# SCH_MIW_PCB_No_PS_2022-01-17.net
KiCad netlist of a schematic drawn in EasyEDA
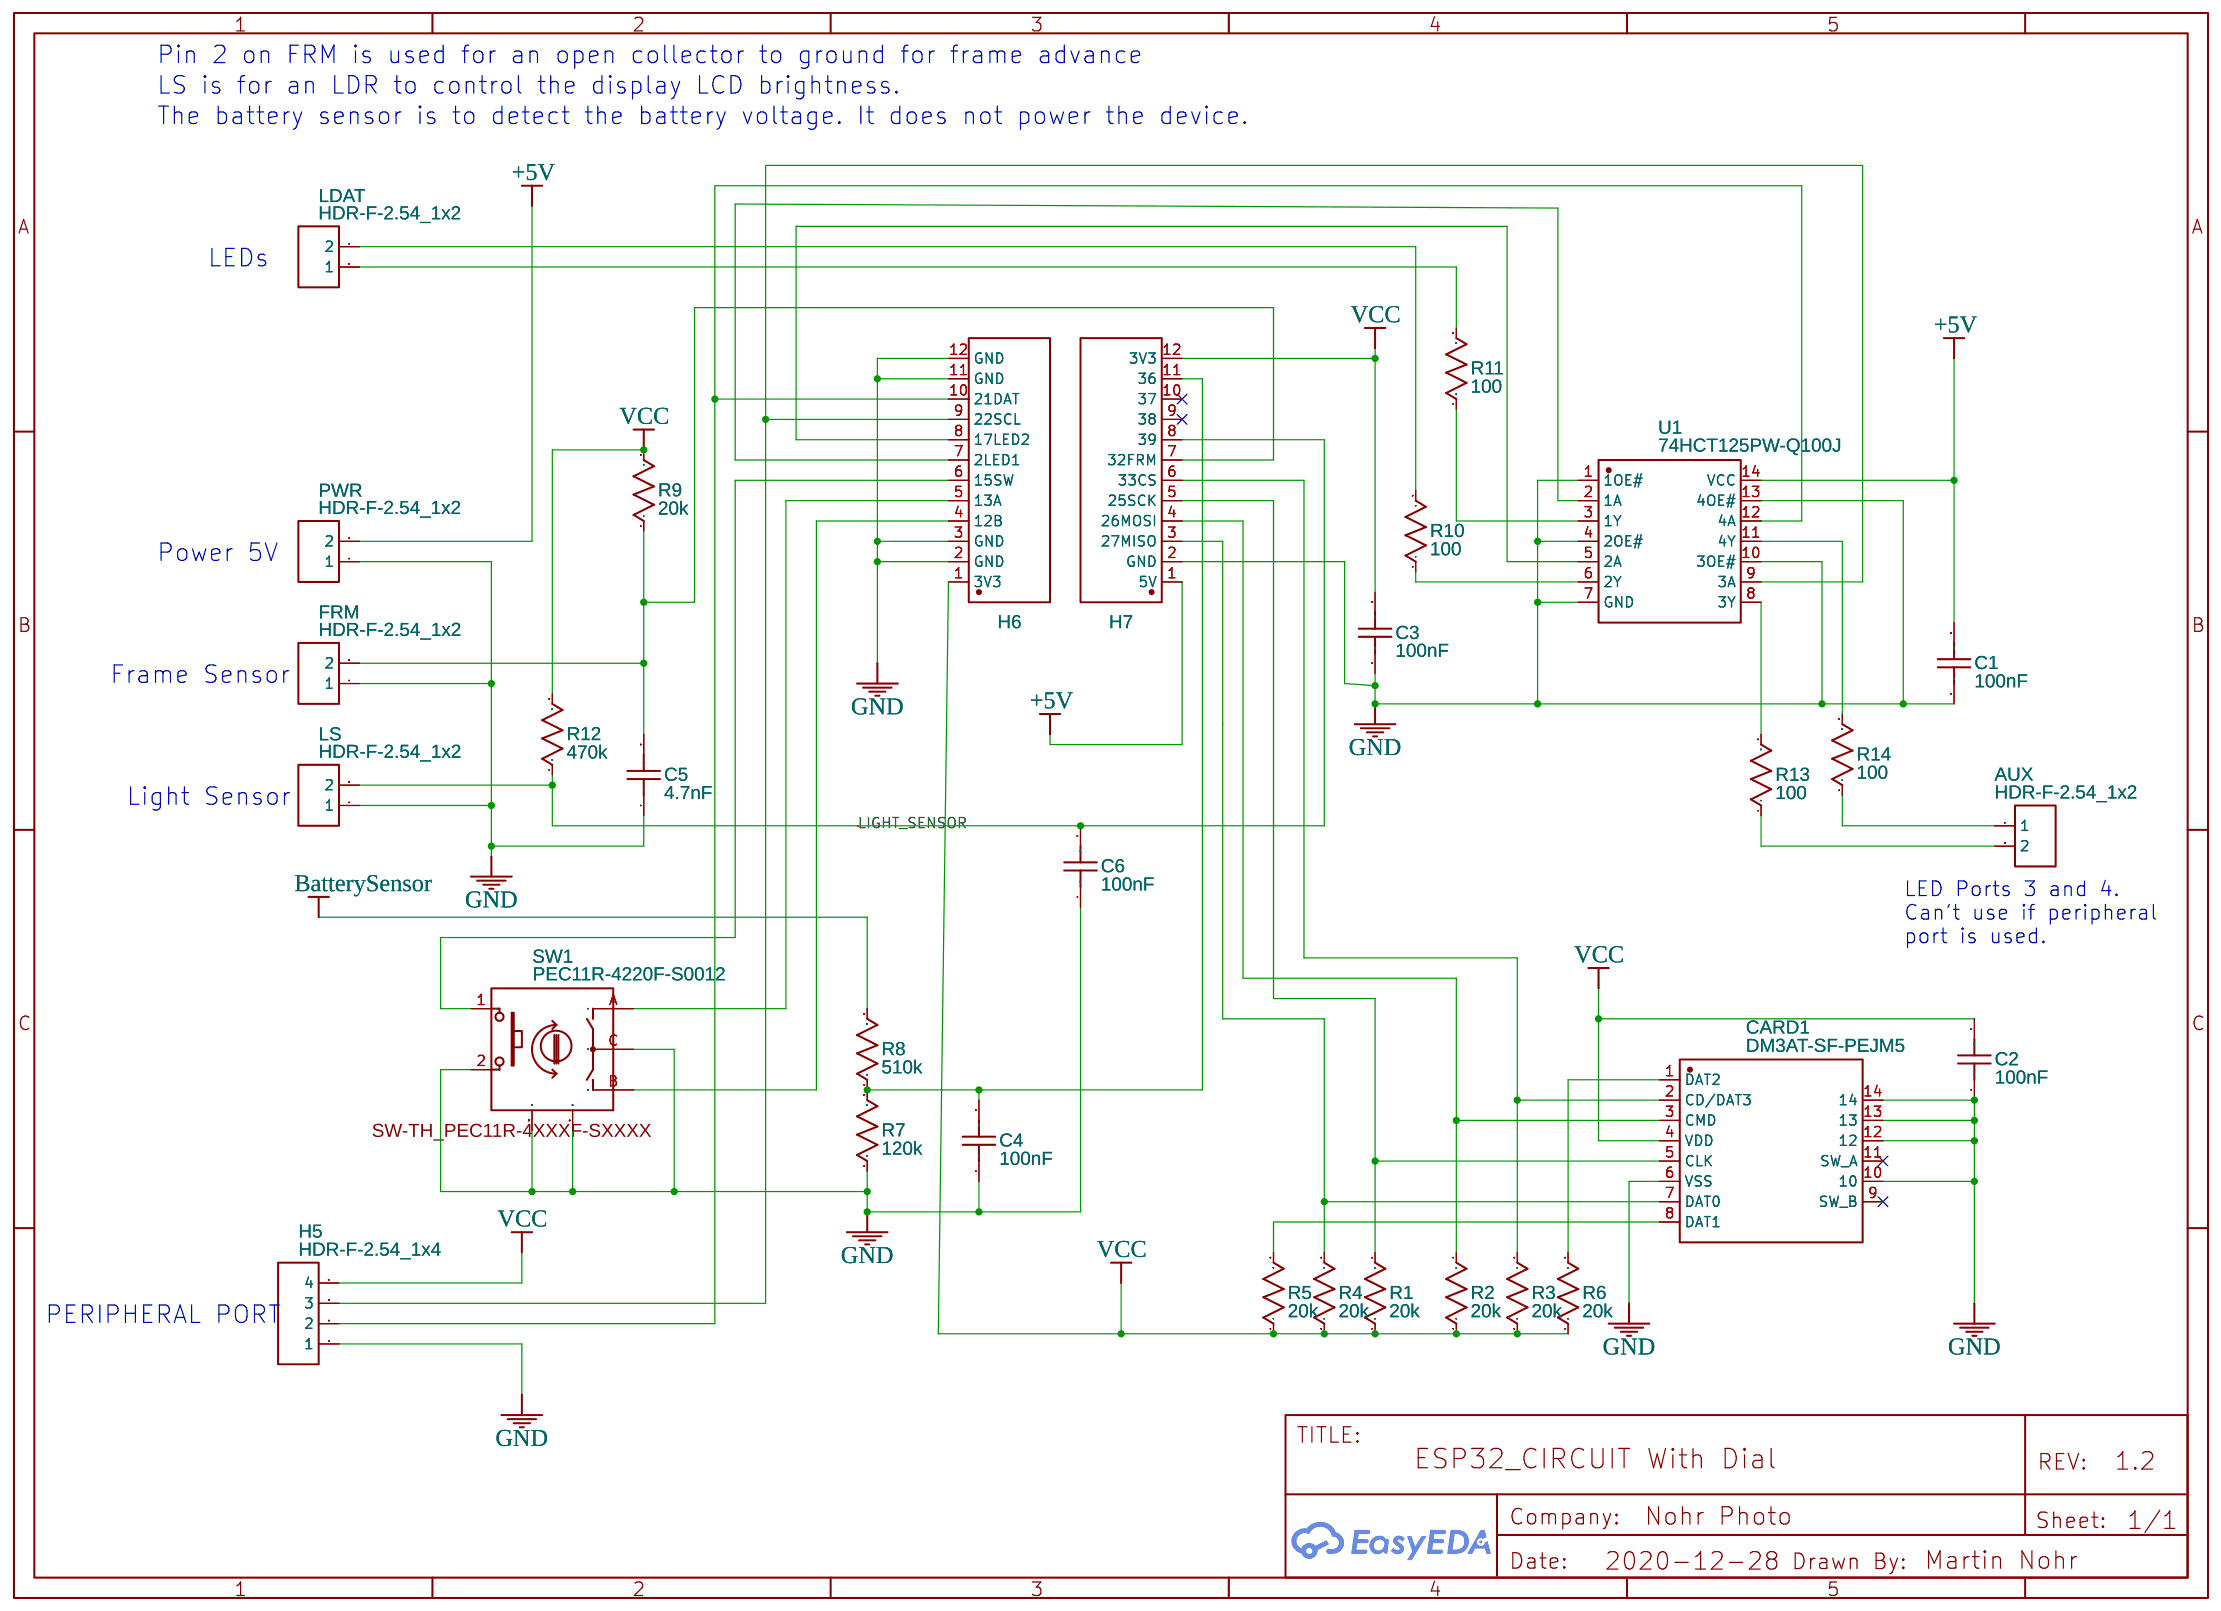
[diagram p0: TTGO_CIRCUIT_PCB]
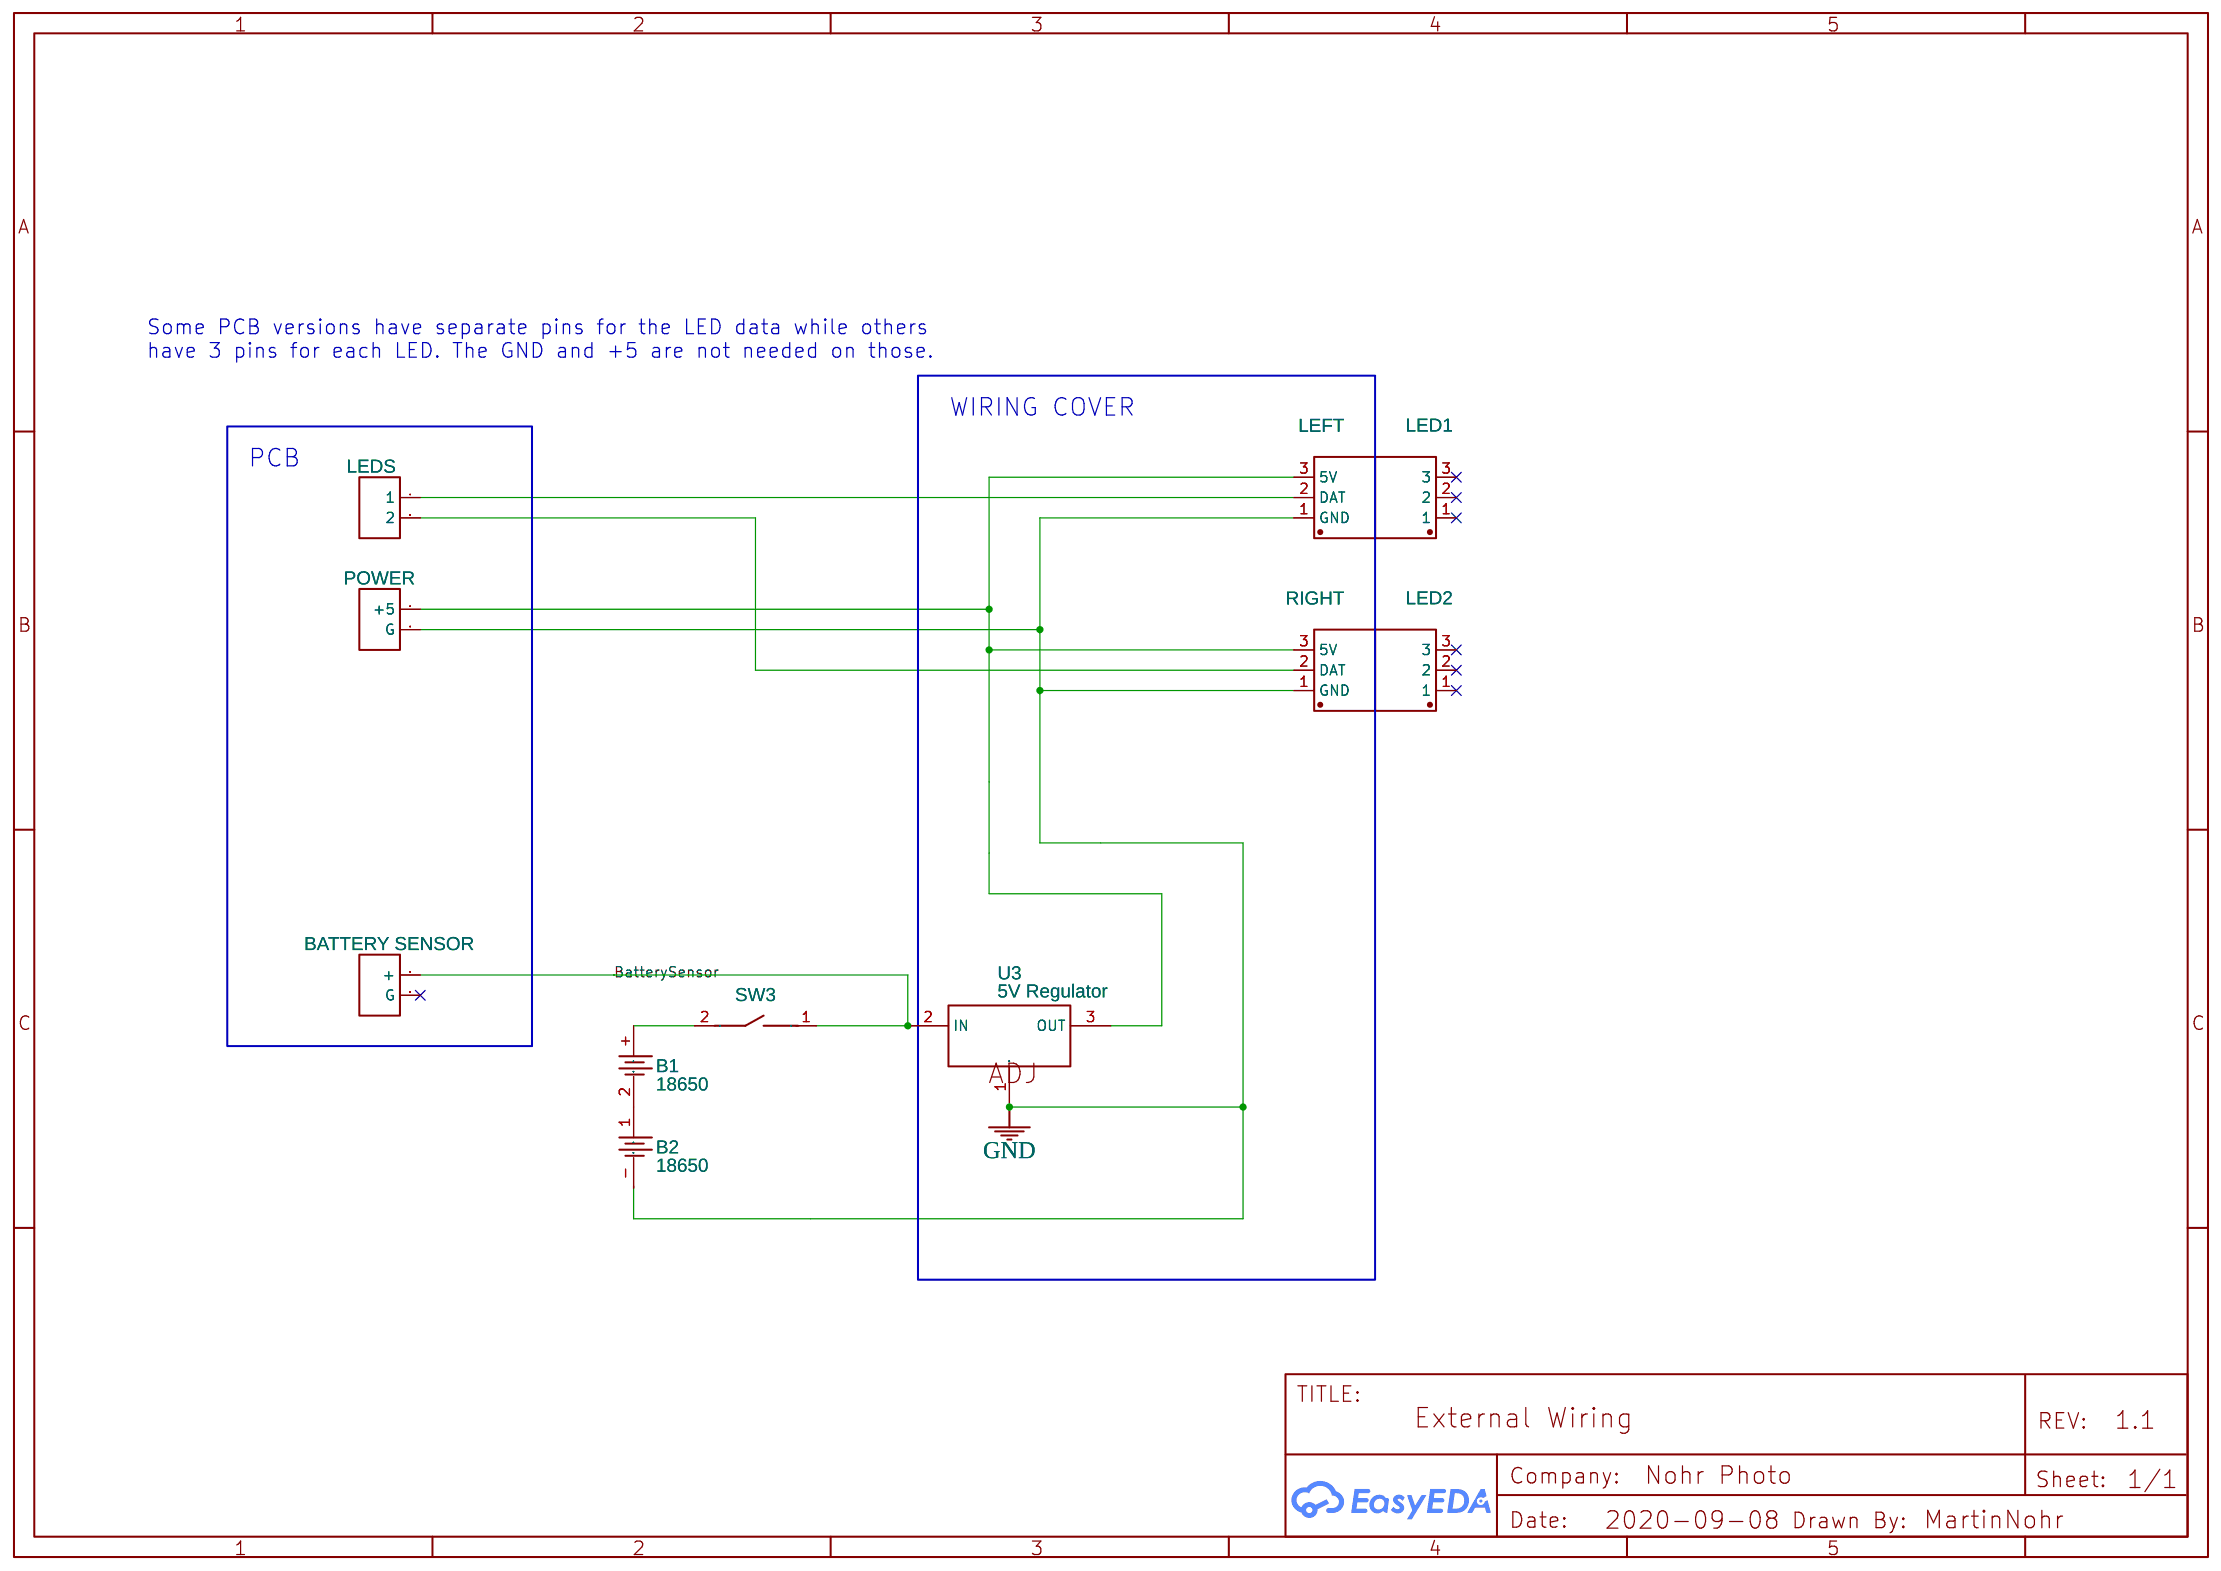
[diagram p1: TTGO External Components]

(export (version "E")
  (design (tool "Eeschema 10.0.6"))
  (components
    (comp (ref "AUX")
      (value "HDR-F-2.54_1x2")
      (fields (field (name "BOM_Supplier Part") "C49661"))
      (libsource (lib "") (part "HDR-F-2.54_1x2"))
    )
    (comp (ref "C1")
      (value "100nF")
      (fields
        (field (name "BOM_Manufacturer Part") "CL10B104KC8NNNC")
        (field (name "BOM_Supplier Part") "C15725")
      )
      (libsource (lib "") (part "CL10B104KB8NFNC"))
    )
    (comp (ref "C2")
      (value "100nF")
      (fields
        (field (name "BOM_Manufacturer Part") "CL10B104KC8NNNC")
        (field (name "BOM_Supplier Part") "C15725")
      )
      (libsource (lib "") (part "CL10B104KB8NFNC"))
    )
    (comp (ref "C3")
      (value "100nF")
      (fields
        (field (name "BOM_Manufacturer Part") "CL10B104KC8NNNC")
        (field (name "BOM_Supplier Part") "C15725")
      )
      (libsource (lib "") (part "CL10B104KB8NFNC"))
    )
    (comp (ref "C4")
      (value "100nF")
      (fields
        (field (name "BOM_Manufacturer Part") "CL10B104KC8NNNC")
        (field (name "BOM_Supplier Part") "C15725")
      )
      (libsource (lib "") (part "CL10B104KB8NFNC"))
    )
    (comp (ref "C5")
      (value "4.7nF")
      (fields
        (field (name "BOM_Manufacturer Part") "CC0603KRX7R9BB472")
        (field (name "BOM_Supplier Part") "C106218")
      )
      (libsource (lib "") (part "CL10B104KB8NFNC"))
    )
    (comp (ref "C6")
      (value "100nF")
      (fields
        (field (name "BOM_Manufacturer Part") "CL10B104KC8NNNC")
        (field (name "BOM_Supplier Part") "C15725")
      )
      (libsource (lib "") (part "CL10B104KB8NFNC"))
    )
    (comp (ref "CARD1")
      (value "DM3AT-SF-PEJM5")
      (fields (field (name "BOM_Supplier Part") "C114218"))
      (libsource (lib "") (part "DM3AT-SF-PEJM5"))
    )
    (comp (ref "FRM")
      (value "HDR-F-2.54_1x2")
      (fields (field (name "BOM_Supplier Part") "C49661"))
      (libsource (lib "") (part "HDR-F-2.54_1x2_3"))
    )
    (comp (ref "H5")
      (value "HDR-F-2.54_1x4")
      (fields (field (name "BOM_Supplier Part") "C225501"))
      (libsource (lib "") (part "HDR-F-2.54_1x4"))
    )
    (comp (ref "H6")
      (value "A2541HWV-12P")
      (fields (field (name "BOM_Supplier Part") "C225509"))
      (libsource (lib "") (part "A2541HWV-12P"))
    )
    (comp (ref "H7")
      (value "A2541HWV-12P")
      (fields (field (name "BOM_Supplier Part") "C225509"))
      (libsource (lib "") (part "A2541HWV-12P_1"))
    )
    (comp (ref "LDAT")
      (value "HDR-F-2.54_1x2")
      (fields (field (name "BOM_Supplier Part") "C49661"))
      (libsource (lib "") (part "HDR-F-2.54_1x2_1"))
    )
    (comp (ref "LS")
      (value "HDR-F-2.54_1x2")
      (fields (field (name "BOM_Supplier Part") "C49661"))
      (libsource (lib "") (part "HDR-F-2.54_1x2_4"))
    )
    (comp (ref "PWR")
      (value "HDR-F-2.54_1x2")
      (fields (field (name "BOM_Supplier Part") "C49661"))
      (libsource (lib "") (part "HDR-F-2.54_1x2_2"))
    )
    (comp (ref "R1")
      (value "20k")
      (fields
        (field (name "BOM_Manufacturer Part") "0603WAF2002T5E")
        (field (name "BOM_Supplier Part") "C4184")
      )
      (libsource (lib "") (part "R_0603_US"))
    )
    (comp (ref "R2")
      (value "20k")
      (fields
        (field (name "BOM_Manufacturer Part") "0603WAF2002T5E")
        (field (name "BOM_Supplier Part") "C4184")
      )
      (libsource (lib "") (part "R_0603_US"))
    )
    (comp (ref "R3")
      (value "20k")
      (fields
        (field (name "BOM_Manufacturer Part") "0603WAF2002T5E")
        (field (name "BOM_Supplier Part") "C4184")
      )
      (libsource (lib "") (part "R_0603_US"))
    )
    (comp (ref "R4")
      (value "20k")
      (fields
        (field (name "BOM_Manufacturer Part") "0603WAF2002T5E")
        (field (name "BOM_Supplier Part") "C4184")
      )
      (libsource (lib "") (part "R_0603_US"))
    )
    (comp (ref "R5")
      (value "20k")
      (fields
        (field (name "BOM_Manufacturer Part") "0603WAF2002T5E")
        (field (name "BOM_Supplier Part") "C4184")
      )
      (libsource (lib "") (part "R_0603_US"))
    )
    (comp (ref "R6")
      (value "20k")
      (fields
        (field (name "BOM_Manufacturer Part") "0603WAF2002T5E")
        (field (name "BOM_Supplier Part") "C4184")
      )
      (libsource (lib "") (part "R_0603_US"))
    )
    (comp (ref "R7")
      (value "120k")
      (fields
        (field (name "BOM_Manufacturer Part") "0603WAF1203T5E")
        (field (name "BOM_Supplier Part") "C25808")
      )
      (libsource (lib "") (part "R_0603_US"))
    )
    (comp (ref "R8")
      (value "510k")
      (fields
        (field (name "BOM_Manufacturer Part") "0603WAF5103T5E")
        (field (name "BOM_Supplier Part") "C23192")
      )
      (libsource (lib "") (part "R_0603_US"))
    )
    (comp (ref "R9")
      (value "20k")
      (fields
        (field (name "BOM_Manufacturer Part") "0603WAF2002T5E")
        (field (name "BOM_Supplier Part") "C4184")
      )
      (libsource (lib "") (part "R_0603_US"))
    )
    (comp (ref "R10")
      (value "100")
      (fields
        (field (name "BOM_Manufacturer Part") "0603WAF1000T5E")
        (field (name "BOM_Supplier Part") "C22775")
      )
      (libsource (lib "") (part "R_0603_US"))
    )
    (comp (ref "R11")
      (value "100")
      (fields
        (field (name "BOM_Manufacturer Part") "0603WAF1000T5E")
        (field (name "BOM_Supplier Part") "C22775")
      )
      (libsource (lib "") (part "R_0603_US"))
    )
    (comp (ref "R12")
      (value "470k")
      (fields
        (field (name "BOM_Manufacturer Part") "0603WAF4703T5E")
        (field (name "BOM_Supplier Part") "C23178")
      )
      (libsource (lib "") (part "R_0603_US"))
    )
    (comp (ref "R13")
      (value "100")
      (fields
        (field (name "BOM_Manufacturer Part") "0603WAF1000T5E")
        (field (name "BOM_Supplier Part") "C22775")
      )
      (libsource (lib "") (part "R_0603_US"))
    )
    (comp (ref "R14")
      (value "100")
      (fields
        (field (name "BOM_Manufacturer Part") "0603WAF1000T5E")
        (field (name "BOM_Supplier Part") "C22775")
      )
      (libsource (lib "") (part "R_0603_US"))
    )
    (comp (ref "SW1")
      (value "PEC11R-4220F-S0012")
      (fields (field (name "BOM_Supplier Part") "C143817"))
      (libsource (lib "") (part "PEC11R-4015F-S0024"))
    )
    (comp (ref "U1")
      (value "74HCT125PW-Q100J")
      (fields (field (name "BOM_Supplier Part") "C545658"))
      (libsource (lib "") (part "74HCT125PW-Q100J"))
    )
    (comp (ref "B1")
      (value "18650")
      (fields (field (name "BOM_Manufacturer Part") "CR1220-2") (field (name "BOM_Supplier Part") "C70381"))
      (libsource (lib "") (part "CR1220-2_1"))
    )
    (comp (ref "B2")
      (value "18650")
      (fields (field (name "BOM_Manufacturer Part") "CR1220-2") (field (name "BOM_Supplier Part") "C70381"))
      (libsource (lib "") (part "CR1220-2"))
    )
    (comp (ref "H1")
      (value "LEDS")
      (fields (field (name "BOM_Supplier Part") "C49661"))
      (libsource (lib "") (part "HDR-F-2.54_1x2_2"))
    )
    (comp (ref "H10")
      (value "POWER")
      (fields (field (name "BOM_Supplier Part") "C49661"))
      (libsource (lib "") (part "HDR-F-2.54_1x2_1"))
    )
    (comp (ref "H12")
      (value "BATTERY SENSOR")
      (fields (field (name "BOM_Supplier Part") "C49661"))
      (libsource (lib "") (part "HDR-F-2.54_1x2"))
    )
    (comp (ref "LED1")
      (value "68000-103HLF")
      (fields (field (name "BOM_Supplier Part") "C168677"))
      (libsource (lib "") (part "68000-103HLF_1"))
    )
    (comp (ref "LED2")
      (value "68000-103HLF")
      (fields (field (name "BOM_Supplier Part") "C168677"))
      (libsource (lib "") (part "68000-103HLF_1"))
    )
    (comp (ref "LEFT")
      (value "68000-103HLF")
      (fields (field (name "BOM_Supplier Part") "C168677"))
      (libsource (lib "") (part "68000-103HLF_2"))
    )
    (comp (ref "RIGHT")
      (value "68000-103HLF")
      (fields (field (name "BOM_Supplier Part") "C168677"))
      (libsource (lib "") (part "68000-103HLF"))
    )
    (comp (ref "SW3")
      (value "SWITCH,6*6*5PLASTIC HEAD,260G, 0.25MM,DIP2")
      (fields
        (field (name "BOM_Manufacturer Part") "Switch,6*6*5Plastic head,260G, 0.25mm,DIP2")
        (field (name "BOM_Supplier Part") "C71845")
      )
      (libsource (lib "") (part "SWITCH,6*6*5PLASTIC HEAD,260G, 0.25MM,DIP2"))
    )
    (comp (ref "U3")
      (value "5V Regulator")
      (fields (field (name "BOM_Manufacturer Part") "LM337D2TG") (field (name "BOM_Supplier Part") "C146782"))
      (libsource (lib "") (part "LM337(TO-263)"))
    )
  )
  (nets
    (net (code "1") (name "+5V") (class "Default")
      (node (ref "C1") (pin "2") (pinfunction "2_2") (pintype "unspecified"))
      (node (ref "H7") (pin "1") (pinfunction "5V_1") (pintype "unspecified"))
      (node (ref "PWR") (pin "2") (pinfunction "2_2") (pintype "input"))
      (node (ref "U1") (pin "14") (pinfunction "VCC_14") (pintype "unspecified"))
    )
    (net (code "2") (name "BatterySensor") (class "Default")
      (node (ref "H12") (pin "1") (pinfunction "+_1") (pintype "input"))
      (node (ref "R8") (pin "2") (pinfunction "2_2") (pintype "unspecified"))
      (node (ref "SW3") (pin "1") (pinfunction "1_1") (pintype "unspecified"))
      (node (ref "U3") (pin "2") (pinfunction "IN_2") (pintype "passive"))
    )
    (net (code "3") (name "GND") (class "Default")
      (node (ref "B2") (pin "-") (pinfunction "2_-") (pintype "input"))
      (node (ref "C1") (pin "1") (pinfunction "1_1") (pintype "unspecified"))
      (node (ref "C2") (pin "1") (pinfunction "1_1") (pintype "unspecified"))
      (node (ref "C3") (pin "1") (pinfunction "1_1") (pintype "unspecified"))
      (node (ref "C4") (pin "1") (pinfunction "1_1") (pintype "unspecified"))
      (node (ref "C5") (pin "1") (pinfunction "1_1") (pintype "unspecified"))
      (node (ref "C6") (pin "1") (pinfunction "1_1") (pintype "unspecified"))
      (node (ref "CARD1") (pin "10") (pinfunction "10_10") (pintype "unspecified"))
      (node (ref "CARD1") (pin "12") (pinfunction "12_12") (pintype "unspecified"))
      (node (ref "CARD1") (pin "13") (pinfunction "13_13") (pintype "unspecified"))
      (node (ref "CARD1") (pin "14") (pinfunction "14_14") (pintype "unspecified"))
      (node (ref "CARD1") (pin "6") (pinfunction "VSS_6") (pintype "unspecified"))
      (node (ref "FRM") (pin "1") (pinfunction "1_1") (pintype "input"))
      (node (ref "H10") (pin "2") (pinfunction "G_2") (pintype "input"))
      (node (ref "H5") (pin "1") (pinfunction "1_1") (pintype "unspecified"))
      (node (ref "H6") (pin "11") (pinfunction "GND_11") (pintype "unspecified"))
      (node (ref "H6") (pin "12") (pinfunction "GND_12") (pintype "unspecified"))
      (node (ref "H6") (pin "2") (pinfunction "GND_2") (pintype "unspecified"))
      (node (ref "H6") (pin "3") (pinfunction "GND_3") (pintype "unspecified"))
      (node (ref "H7") (pin "2") (pinfunction "GND_2") (pintype "unspecified"))
      (node (ref "LEFT") (pin "1") (pinfunction "GND_1") (pintype "unspecified"))
      (node (ref "LS") (pin "1") (pinfunction "1_1") (pintype "input"))
      (node (ref "PWR") (pin "1") (pinfunction "1_1") (pintype "input"))
      (node (ref "R7") (pin "1") (pinfunction "1_1") (pintype "unspecified"))
      (node (ref "RIGHT") (pin "1") (pinfunction "GND_1") (pintype "unspecified"))
      (node (ref "SW1") (pin "2") (pinfunction "2_2") (pintype "unspecified"))
      (node (ref "SW1") (pin "C") (pinfunction "C_C") (pintype "unspecified"))
      (node (ref "SW1") (pin "MT1") (pinfunction "MT1_MT1") (pintype "unspecified"))
      (node (ref "SW1") (pin "MT2") (pinfunction "MT2_MT2") (pintype "unspecified"))
      (node (ref "U1") (pin "1") (pinfunction "1OE#_1") (pintype "unspecified"))
      (node (ref "U1") (pin "10") (pinfunction "3OE#_10") (pintype "unspecified"))
      (node (ref "U1") (pin "13") (pinfunction "4OE#_13") (pintype "unspecified"))
      (node (ref "U1") (pin "4") (pinfunction "2OE#_4") (pintype "unspecified"))
      (node (ref "U1") (pin "7") (pinfunction "GND_7") (pintype "unspecified"))
      (node (ref "U3") (pin "1") (pinfunction "ADJ_1") (pintype "passive"))
    )
    (net (code "4") (name "LIGHT_SENSOR") (class "Default")
      (node (ref "C6") (pin "2") (pinfunction "2_2") (pintype "unspecified"))
      (node (ref "H7") (pin "8") (pinfunction "39_8") (pintype "unspecified"))
      (node (ref "LS") (pin "2") (pinfunction "2_2") (pintype "input"))
      (node (ref "R12") (pin "1") (pinfunction "1_1") (pintype "unspecified"))
    )
    (net (code "5") (name "Net-(AUX-Pad1)") (class "Default")
      (node (ref "AUX") (pin "1") (pinfunction "1_1") (pintype "input"))
      (node (ref "R14") (pin "1") (pinfunction "1_1") (pintype "unspecified"))
    )
    (net (code "6") (name "Net-(AUX-Pad2)") (class "Default")
      (node (ref "AUX") (pin "2") (pinfunction "2_2") (pintype "input"))
      (node (ref "R13") (pin "1") (pinfunction "1_1") (pintype "unspecified"))
    )
    (net (code "7") (name "Net-(B1-1)") (class "Default")
      (node (ref "B1") (pin "+") (pinfunction "1_+") (pintype "input"))
      (node (ref "SW3") (pin "2") (pinfunction "2_2") (pintype "unspecified"))
    )
    (net (code "8") (name "Net-(B1-Pad2)") (class "Default")
      (node (ref "B1") (pin "2") (pinfunction "2_2") (pintype "input"))
      (node (ref "B2") (pin "1") (pinfunction "1_1") (pintype "input"))
    )
    (net (code "9") (name "Net-(CARD1-CD{slash}DAT3)") (class "Default")
      (node (ref "CARD1") (pin "2") (pinfunction "CD/DAT3_2") (pintype "unspecified"))
      (node (ref "H7") (pin "6") (pinfunction "33CS_6") (pintype "unspecified"))
      (node (ref "R3") (pin "2") (pinfunction "2_2") (pintype "unspecified"))
    )
    (net (code "10") (name "Net-(CARD1-CLK)") (class "Default")
      (node (ref "CARD1") (pin "5") (pinfunction "CLK_5") (pintype "unspecified"))
      (node (ref "H7") (pin "5") (pinfunction "25SCK_5") (pintype "unspecified"))
      (node (ref "R1") (pin "2") (pinfunction "2_2") (pintype "unspecified"))
    )
    (net (code "11") (name "Net-(CARD1-CMD)") (class "Default")
      (node (ref "CARD1") (pin "3") (pinfunction "CMD_3") (pintype "unspecified"))
      (node (ref "H7") (pin "4") (pinfunction "26MOSI_4") (pintype "unspecified"))
      (node (ref "R2") (pin "2") (pinfunction "2_2") (pintype "unspecified"))
    )
    (net (code "12") (name "Net-(CARD1-DAT0)") (class "Default")
      (node (ref "CARD1") (pin "7") (pinfunction "DAT0_7") (pintype "unspecified"))
      (node (ref "H7") (pin "3") (pinfunction "27MISO_3") (pintype "unspecified"))
      (node (ref "R4") (pin "2") (pinfunction "2_2") (pintype "unspecified"))
    )
    (net (code "13") (name "Net-(CARD1-DAT1)") (class "Default")
      (node (ref "CARD1") (pin "8") (pinfunction "DAT1_8") (pintype "unspecified"))
      (node (ref "R5") (pin "2") (pinfunction "2_2") (pintype "unspecified"))
    )
    (net (code "14") (name "Net-(CARD1-DAT2)") (class "Default")
      (node (ref "CARD1") (pin "1") (pinfunction "DAT2_1") (pintype "unspecified"))
      (node (ref "R6") (pin "2") (pinfunction "2_2") (pintype "unspecified"))
    )
    (net (code "15") (name "Net-(H6-2LED1)") (class "Default")
      (node (ref "H6") (pin "7") (pinfunction "2LED1_7") (pintype "unspecified"))
      (node (ref "U1") (pin "2") (pinfunction "1A_2") (pintype "unspecified"))
    )
    (net (code "16") (name "Net-(H6-12B)") (class "Default")
      (node (ref "H6") (pin "4") (pinfunction "12B_4") (pintype "unspecified"))
      (node (ref "SW1") (pin "B") (pinfunction "B_B") (pintype "unspecified"))
    )
    (net (code "17") (name "Net-(H6-13A)") (class "Default")
      (node (ref "H6") (pin "5") (pinfunction "13A_5") (pintype "unspecified"))
      (node (ref "SW1") (pin "A") (pinfunction "A_A") (pintype "unspecified"))
    )
    (net (code "18") (name "Net-(H6-15SW)") (class "Default")
      (node (ref "H6") (pin "6") (pinfunction "15SW_6") (pintype "unspecified"))
      (node (ref "SW1") (pin "1") (pinfunction "1_1") (pintype "unspecified"))
    )
    (net (code "19") (name "Net-(H6-17LED2)") (class "Default")
      (node (ref "H6") (pin "8") (pinfunction "17LED2_8") (pintype "unspecified"))
      (node (ref "U1") (pin "5") (pinfunction "2A_5") (pintype "unspecified"))
    )
    (net (code "20") (name "Net-(H6-21DAT)") (class "Default")
      (node (ref "H5") (pin "2") (pinfunction "2_2") (pintype "unspecified"))
      (node (ref "H6") (pin "10") (pinfunction "21DAT_10") (pintype "unspecified"))
      (node (ref "U1") (pin "12") (pinfunction "4A_12") (pintype "unspecified"))
    )
    (net (code "21") (name "Net-(H6-22SCL)") (class "Default")
      (node (ref "H5") (pin "3") (pinfunction "3_3") (pintype "unspecified"))
      (node (ref "H6") (pin "9") (pinfunction "22SCL_9") (pintype "unspecified"))
      (node (ref "U1") (pin "9") (pinfunction "3A_9") (pintype "unspecified"))
    )
    (net (code "22") (name "Net-(H7-32FRM)") (class "Default")
      (node (ref "C5") (pin "2") (pinfunction "2_2") (pintype "unspecified"))
      (node (ref "FRM") (pin "2") (pinfunction "2_2") (pintype "input"))
      (node (ref "H7") (pin "7") (pinfunction "32FRM_7") (pintype "unspecified"))
      (node (ref "R9") (pin "1") (pinfunction "1_1") (pintype "unspecified"))
    )
    (net (code "23") (name "Net-(H7-36)") (class "Default")
      (node (ref "C4") (pin "2") (pinfunction "2_2") (pintype "unspecified"))
      (node (ref "H7") (pin "11") (pinfunction "36_11") (pintype "unspecified"))
      (node (ref "R7") (pin "2") (pinfunction "2_2") (pintype "unspecified"))
      (node (ref "R8") (pin "1") (pinfunction "1_1") (pintype "unspecified"))
    )
    (net (code "24") (name "Net-(H10-+5)") (class "Default")
      (node (ref "H10") (pin "1") (pinfunction "+5_1") (pintype "input"))
      (node (ref "LEFT") (pin "3") (pinfunction "5V_3") (pintype "unspecified"))
      (node (ref "RIGHT") (pin "3") (pinfunction "5V_3") (pintype "unspecified"))
      (node (ref "U3") (pin "3") (pinfunction "OUT_3") (pintype "passive"))
    )
    (net (code "25") (name "Net-(LDAT-Pad1)") (class "Default")
      (node (ref "LDAT") (pin "1") (pinfunction "1_1") (pintype "input"))
      (node (ref "R11") (pin "2") (pinfunction "2_2") (pintype "unspecified"))
    )
    (net (code "26") (name "Net-(LDAT-Pad2)") (class "Default")
      (node (ref "LDAT") (pin "2") (pinfunction "2_2") (pintype "input"))
      (node (ref "R10") (pin "2") (pinfunction "2_2") (pintype "unspecified"))
    )
    (net (code "27") (name "Net-(LEFT-DAT)") (class "Default")
      (node (ref "H1") (pin "1") (pinfunction "1_1") (pintype "input"))
      (node (ref "LEFT") (pin "2") (pinfunction "DAT_2") (pintype "unspecified"))
    )
    (net (code "28") (name "Net-(RIGHT-DAT)") (class "Default")
      (node (ref "H1") (pin "2") (pinfunction "2_2") (pintype "input"))
      (node (ref "RIGHT") (pin "2") (pinfunction "DAT_2") (pintype "unspecified"))
    )
    (net (code "29") (name "Net-(U1-1Y)") (class "Default")
      (node (ref "R11") (pin "1") (pinfunction "1_1") (pintype "unspecified"))
      (node (ref "U1") (pin "3") (pinfunction "1Y_3") (pintype "unspecified"))
    )
    (net (code "30") (name "Net-(U1-2Y)") (class "Default")
      (node (ref "R10") (pin "1") (pinfunction "1_1") (pintype "unspecified"))
      (node (ref "U1") (pin "6") (pinfunction "2Y_6") (pintype "unspecified"))
    )
    (net (code "31") (name "Net-(U1-3Y)") (class "Default")
      (node (ref "R13") (pin "2") (pinfunction "2_2") (pintype "unspecified"))
      (node (ref "U1") (pin "8") (pinfunction "3Y_8") (pintype "unspecified"))
    )
    (net (code "32") (name "Net-(U1-4Y)") (class "Default")
      (node (ref "R14") (pin "2") (pinfunction "2_2") (pintype "unspecified"))
      (node (ref "U1") (pin "11") (pinfunction "4Y_11") (pintype "unspecified"))
    )
    (net (code "33") (name "VCC") (class "Default")
      (node (ref "C2") (pin "2") (pinfunction "2_2") (pintype "unspecified"))
      (node (ref "C3") (pin "2") (pinfunction "2_2") (pintype "unspecified"))
      (node (ref "CARD1") (pin "4") (pinfunction "VDD_4") (pintype "unspecified"))
      (node (ref "H5") (pin "4") (pinfunction "4_4") (pintype "unspecified"))
      (node (ref "H6") (pin "1") (pinfunction "3V3_1") (pintype "unspecified"))
      (node (ref "H7") (pin "12") (pinfunction "3V3_12") (pintype "unspecified"))
      (node (ref "R1") (pin "1") (pinfunction "1_1") (pintype "unspecified"))
      (node (ref "R12") (pin "2") (pinfunction "2_2") (pintype "unspecified"))
      (node (ref "R2") (pin "1") (pinfunction "1_1") (pintype "unspecified"))
      (node (ref "R3") (pin "1") (pinfunction "1_1") (pintype "unspecified"))
      (node (ref "R4") (pin "1") (pinfunction "1_1") (pintype "unspecified"))
      (node (ref "R5") (pin "1") (pinfunction "1_1") (pintype "unspecified"))
      (node (ref "R6") (pin "1") (pinfunction "1_1") (pintype "unspecified"))
      (node (ref "R9") (pin "2") (pinfunction "2_2") (pintype "unspecified"))
    )
    (net (code "34") (name "unconnected-(CARD1-SW_A-Pad11)") (class "Default")
      (node (ref "CARD1") (pin "11") (pinfunction "SW_A_11") (pintype "unspecified+no_connect"))
    )
    (net (code "35") (name "unconnected-(CARD1-SW_B-Pad9)") (class "Default")
      (node (ref "CARD1") (pin "9") (pinfunction "SW_B_9") (pintype "unspecified+no_connect"))
    )
    (net (code "36") (name "unconnected-(H7-37-Pad10)") (class "Default")
      (node (ref "H7") (pin "10") (pinfunction "37_10") (pintype "unspecified+no_connect"))
    )
    (net (code "37") (name "unconnected-(H7-38-Pad9)") (class "Default")
      (node (ref "H7") (pin "9") (pinfunction "38_9") (pintype "unspecified+no_connect"))
    )
    (net (code "38") (name "unconnected-(H12-G-Pad2)") (class "Default")
      (node (ref "H12") (pin "2") (pinfunction "G_2") (pintype "input+no_connect"))
    )
    (net (code "39") (name "unconnected-(LED1-Pad1)") (class "Default")
      (node (ref "LED1") (pin "1") (pinfunction "1_1") (pintype "unspecified+no_connect"))
    )
    (net (code "40") (name "unconnected-(LED1-Pad2)") (class "Default")
      (node (ref "LED1") (pin "2") (pinfunction "2_2") (pintype "unspecified+no_connect"))
    )
    (net (code "41") (name "unconnected-(LED1-Pad3)") (class "Default")
      (node (ref "LED1") (pin "3") (pinfunction "3_3") (pintype "unspecified+no_connect"))
    )
    (net (code "42") (name "unconnected-(LED2-Pad1)") (class "Default")
      (node (ref "LED2") (pin "1") (pinfunction "1_1") (pintype "unspecified+no_connect"))
    )
    (net (code "43") (name "unconnected-(LED2-Pad2)") (class "Default")
      (node (ref "LED2") (pin "2") (pinfunction "2_2") (pintype "unspecified+no_connect"))
    )
    (net (code "44") (name "unconnected-(LED2-Pad3)") (class "Default")
      (node (ref "LED2") (pin "3") (pinfunction "3_3") (pintype "unspecified+no_connect"))
    )
  )
)
